# PinBuchse.net
KiCad netlist of a schematic drawn in EAGLE
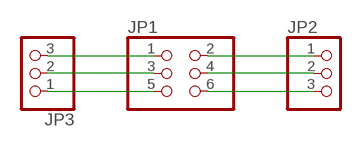
[diagram p0: schematic, sheet 1]

(export (version "E")
  (design (tool "Eeschema 10.0.6"))
  (components
    (comp (ref "JP1")
      (value "PINHD-2X3")
      (footprint "eagle-import:2X03")
      (libsource (lib "eagle-import") (part "PINHD-2X3"))
    )
    (comp (ref "JP2")
      (value "PINHD-1X3")
      (footprint "eagle-import:1X03")
      (libsource (lib "eagle-import") (part "PINHD-1X3"))
    )
    (comp (ref "JP3")
      (value "PINHD-1X3")
      (footprint "eagle-import:1X03")
      (libsource (lib "eagle-import") (part "PINHD-1X3"))
    )
  )
  (nets
    (net (code "1") (name "Net-(JP1-Pad1)") (class "Default")
      (node (ref "JP1") (pin "1") (pinfunction "1_1") (pintype "passive"))
      (node (ref "JP3") (pin "3") (pinfunction "3_3") (pintype "passive"))
    )
    (net (code "2") (name "Net-(JP1-Pad2)") (class "Default")
      (node (ref "JP1") (pin "2") (pinfunction "2_2") (pintype "passive"))
      (node (ref "JP2") (pin "1") (pinfunction "1_1") (pintype "passive"))
    )
    (net (code "3") (name "Net-(JP1-Pad3)") (class "Default")
      (node (ref "JP1") (pin "3") (pinfunction "3_3") (pintype "passive"))
      (node (ref "JP3") (pin "2") (pinfunction "2_2") (pintype "passive"))
    )
    (net (code "4") (name "Net-(JP1-Pad4)") (class "Default")
      (node (ref "JP1") (pin "4") (pinfunction "4_4") (pintype "passive"))
      (node (ref "JP2") (pin "2") (pinfunction "2_2") (pintype "passive"))
    )
    (net (code "5") (name "Net-(JP1-Pad5)") (class "Default")
      (node (ref "JP1") (pin "5") (pinfunction "5_5") (pintype "passive"))
      (node (ref "JP3") (pin "1") (pinfunction "1_1") (pintype "passive"))
    )
    (net (code "6") (name "Net-(JP1-Pad6)") (class "Default")
      (node (ref "JP1") (pin "6") (pinfunction "6_6") (pintype "passive"))
      (node (ref "JP2") (pin "3") (pinfunction "3_3") (pintype "passive"))
    )
  )
)
